# tempSensor.net
KiCad netlist of a schematic drawn in EAGLE
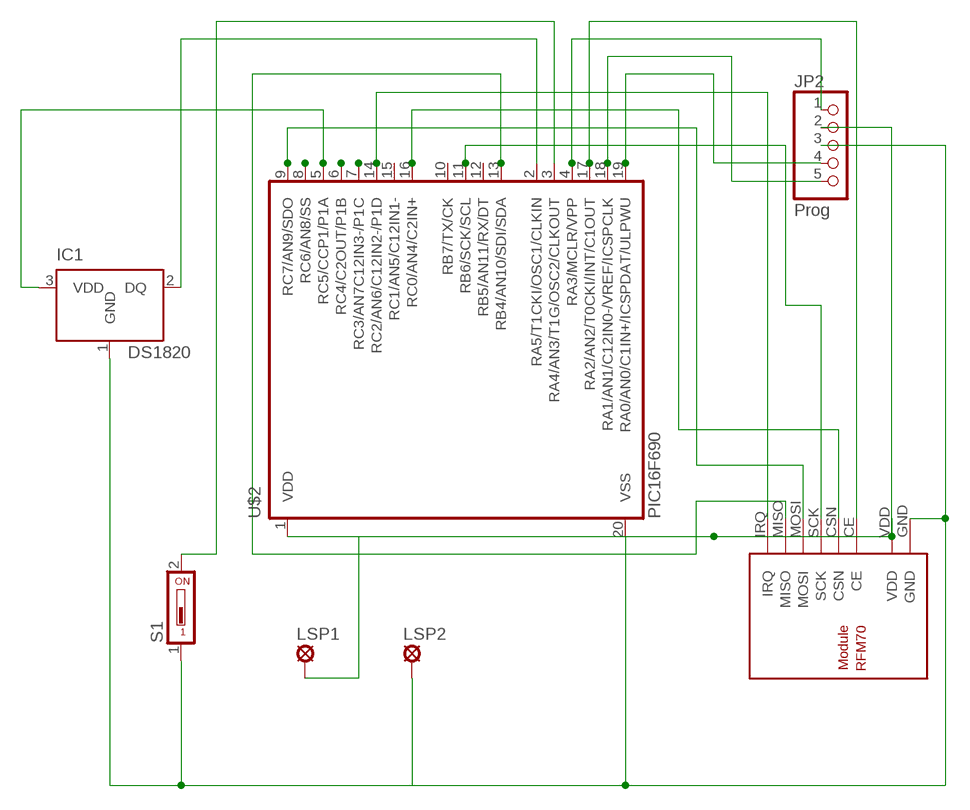
[diagram p0: schematic, sheet 1]

(export (version "E")
  (design (tool "Eeschema 10.0.6"))
  (components
    (comp (ref "IC1")
      (value "DS1820")
      (footprint "eagle-import:TO-92")
      (libsource (lib "eagle-import") (part "DS1820"))
    )
    (comp (ref "JP2")
      (value "Prog")
      (footprint "eagle-import:1X05")
      (libsource (lib "eagle-import") (part "PINHD-1X5"))
    )
    (comp (ref "LSP1")
      (value "LSP11")
      (footprint "eagle-import:LSP11")
      (libsource (lib "eagle-import") (part "LSP11"))
    )
    (comp (ref "LSP2")
      (value "LSP11")
      (footprint "eagle-import:LSP11")
      (libsource (lib "eagle-import") (part "LSP11"))
    )
    (comp (ref "S1")
      (value "SD4-01")
      (footprint "eagle-import:SD4-01")
      (libsource (lib "eagle-import") (part "SD4-01"))
    )
    (comp (ref "U$1")
      (value "RFM70")
      (footprint "eagle-import:RFM70")
      (libsource (lib "eagle-import") (part "RFM70"))
    )
    (comp (ref "U$2")
      (value "PIC16F690")
      (footprint "eagle-import:SSOP20")
      (libsource (lib "eagle-import") (part "PIC16F690"))
    )
  )
  (nets
    (net (code "1") (name "Net-(IC1-DQ)") (class "Default")
      (node (ref "IC1") (pin "2") (pinfunction "DQ_2") (pintype "output"))
      (node (ref "U$2") (pin "2") (pinfunction "RA5/T1CKI/OSC1/CLKIN_2") (pintype "bidirectional"))
    )
    (net (code "2") (name "Net-(IC1-GND)") (class "Default")
      (node (ref "IC1") (pin "1") (pinfunction "GND_1") (pintype "power_in"))
      (node (ref "JP2") (pin "3") (pinfunction "3_3") (pintype "passive"))
      (node (ref "LSP2") (pin "MP") (pinfunction "MP_MP") (pintype "passive"))
      (node (ref "S1") (pin "1") (pinfunction "1_1") (pintype "passive"))
      (node (ref "U$1") (pin "GND") (pinfunction "GND_GND") (pintype "power_in"))
      (node (ref "U$2") (pin "20") (pinfunction "VSS_20") (pintype "power_in"))
    )
    (net (code "3") (name "Net-(IC1-VDD)") (class "Default")
      (node (ref "IC1") (pin "3") (pinfunction "VDD_3") (pintype "input"))
      (node (ref "U$2") (pin "5") (pinfunction "RC5/CCP1/P1A_5") (pintype "bidirectional"))
    )
    (net (code "4") (name "Net-(U$2-RA0{slash}AN0{slash}C1IN+{slash}ICSPDAT{slash}ULPWU)") (class "Default")
      (node (ref "JP2") (pin "4") (pinfunction "4_4") (pintype "passive"))
      (node (ref "U$2") (pin "19") (pinfunction "RA0/AN0/C1IN+/ICSPDAT/ULPWU_19") (pintype "bidirectional"))
    )
    (net (code "5") (name "Net-(U$2-RA1{slash}AN1{slash}C12IN0-{slash}VREF{slash}ICSPCLK)") (class "Default")
      (node (ref "JP2") (pin "5") (pinfunction "5_5") (pintype "passive"))
      (node (ref "U$2") (pin "18") (pinfunction "RA1/AN1/C12IN0-/VREF/ICSPCLK_18") (pintype "bidirectional"))
    )
    (net (code "6") (name "Net-(U$2-RA2{slash}AN2{slash}T0CKI{slash}INT{slash}C1OUT)") (class "Default")
      (node (ref "U$1") (pin "CE") (pinfunction "CE_CE") (pintype "bidirectional"))
      (node (ref "U$2") (pin "17") (pinfunction "RA2/AN2/T0CKI/INT/C1OUT_17") (pintype "bidirectional"))
    )
    (net (code "7") (name "Net-(U$2-RA3{slash}MCLR{slash}VPP)") (class "Default")
      (node (ref "JP2") (pin "1") (pinfunction "1_1") (pintype "passive"))
      (node (ref "U$2") (pin "4") (pinfunction "RA3/MCLR/VPP_4") (pintype "bidirectional"))
    )
    (net (code "8") (name "Net-(U$2-RA4{slash}AN3{slash}T1G{slash}OSC2{slash}CLKOUT)") (class "Default")
      (node (ref "S1") (pin "2") (pinfunction "2_2") (pintype "passive"))
      (node (ref "U$2") (pin "3") (pinfunction "RA4/AN3/T1G/OSC2/CLKOUT_3") (pintype "bidirectional"))
    )
    (net (code "9") (name "Net-(U$2-RB4{slash}AN10{slash}SDI{slash}SDA)") (class "Default")
      (node (ref "U$1") (pin "MISO") (pinfunction "MISO_MISO") (pintype "bidirectional"))
      (node (ref "U$2") (pin "13") (pinfunction "RB4/AN10/SDI/SDA_13") (pintype "bidirectional"))
    )
    (net (code "10") (name "Net-(U$2-RB6{slash}SCK{slash}SCL)") (class "Default")
      (node (ref "U$1") (pin "SCK") (pinfunction "SCK_SCK") (pintype "bidirectional"))
      (node (ref "U$2") (pin "11") (pinfunction "RB6/SCK/SCL_11") (pintype "bidirectional"))
    )
    (net (code "11") (name "Net-(U$2-RC0{slash}AN4{slash}C2IN+)") (class "Default")
      (node (ref "U$1") (pin "CSN") (pinfunction "CSN_CSN") (pintype "bidirectional"))
      (node (ref "U$2") (pin "16") (pinfunction "RC0/AN4/C2IN+_16") (pintype "bidirectional"))
    )
    (net (code "12") (name "Net-(U$2-RC2{slash}AN6{slash}C12IN2-{slash}P1D)") (class "Default")
      (node (ref "U$1") (pin "IRQ") (pinfunction "IRQ_IRQ") (pintype "bidirectional"))
      (node (ref "U$2") (pin "14") (pinfunction "RC2/AN6/C12IN2-/P1D_14") (pintype "bidirectional"))
    )
    (net (code "13") (name "Net-(U$2-RC7{slash}AN9{slash}SDO)") (class "Default")
      (node (ref "U$1") (pin "MOSI") (pinfunction "MOSI_MOSI") (pintype "bidirectional"))
      (node (ref "U$2") (pin "9") (pinfunction "RC7/AN9/SDO_9") (pintype "bidirectional"))
    )
    (net (code "14") (name "Net-(U$2-VDD)") (class "Default")
      (node (ref "JP2") (pin "2") (pinfunction "2_2") (pintype "passive"))
      (node (ref "LSP1") (pin "MP") (pinfunction "MP_MP") (pintype "passive"))
      (node (ref "U$1") (pin "VDD") (pinfunction "VDD_VDD") (pintype "power_in"))
      (node (ref "U$2") (pin "1") (pinfunction "VDD_1") (pintype "power_in"))
    )
    (net (code "15") (name "unconnected-(U$2-RB5{slash}AN11{slash}RX{slash}DT-Pad12)") (class "Default")
      (node (ref "U$2") (pin "12") (pinfunction "RB5/AN11/RX/DT_12") (pintype "bidirectional"))
    )
    (net (code "16") (name "unconnected-(U$2-RB7{slash}TX{slash}CK-Pad10)") (class "Default")
      (node (ref "U$2") (pin "10") (pinfunction "RB7/TX/CK_10") (pintype "bidirectional"))
    )
    (net (code "17") (name "unconnected-(U$2-RC1{slash}AN5{slash}C12IN1--Pad15)") (class "Default")
      (node (ref "U$2") (pin "15") (pinfunction "RC1/AN5/C12IN1-_15") (pintype "bidirectional"))
    )
    (net (code "18") (name "unconnected-(U$2-RC3{slash}AN7C12IN3-{slash}P1C-Pad7)") (class "Default")
      (node (ref "U$2") (pin "7") (pinfunction "RC3/AN7C12IN3-/P1C_7") (pintype "bidirectional"))
    )
    (net (code "19") (name "unconnected-(U$2-RC4{slash}C2OUT{slash}P1B-Pad6)") (class "Default")
      (node (ref "U$2") (pin "6") (pinfunction "RC4/C2OUT/P1B_6") (pintype "bidirectional"))
    )
    (net (code "20") (name "unconnected-(U$2-RC6{slash}AN8{slash}SS-Pad8)") (class "Default")
      (node (ref "U$2") (pin "8") (pinfunction "RC6/AN8/SS_8") (pintype "bidirectional"))
    )
  )
)
